# BackPlane.net
KiCad netlist of a schematic drawn in EAGLE
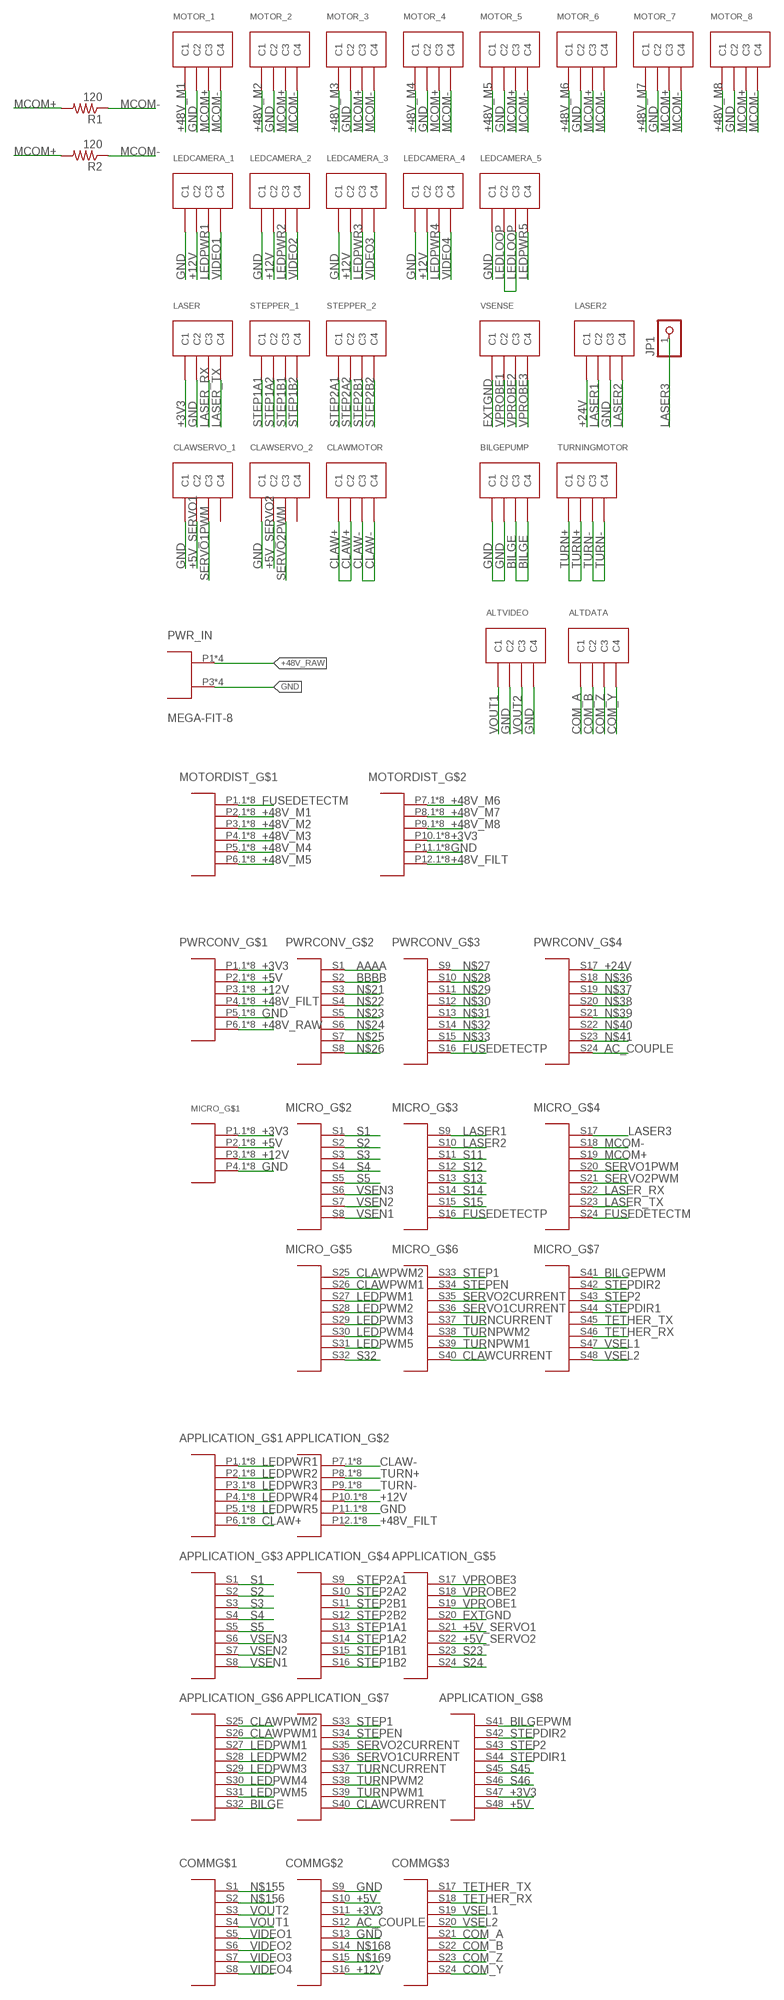
[diagram p0: schematic, sheet 1]

(export (version "E")
  (design (tool "Eeschema 10.0.6"))
  (components
    (comp (ref "ALTDATA")
      (value "MICRO-FIT-4-SMD-PART")
      (footprint "eagle-import:MIRCO-FIT-4-SMD")
      (libsource (lib "eagle-import") (part "MICRO-FIT-4-SMD-PART"))
    )
    (comp (ref "ALTVIDEO")
      (value "MICRO-FIT-4-SMD-PART")
      (footprint "eagle-import:MIRCO-FIT-4-SMD")
      (libsource (lib "eagle-import") (part "MICRO-FIT-4-SMD-PART"))
    )
    (comp (ref "APPLICATION_")
      (value "TEN60-P6-S24-S24-P6-VERT")
      (footprint "eagle-import:TEN60-P6-S24-S24-P6-VERT")
      (libsource (lib "eagle-import") (part "TEN60-P6-S24-S24-P6-VERT"))
    )
    (comp (ref "BILGEPUMP")
      (value "MICRO-FIT-4-SMD-PART")
      (footprint "eagle-import:MIRCO-FIT-4-SMD")
      (libsource (lib "eagle-import") (part "MICRO-FIT-4-SMD-PART"))
    )
    (comp (ref "CLAWMOTOR")
      (value "MICRO-FIT-4-SMD-PART")
      (footprint "eagle-import:MIRCO-FIT-4-SMD")
      (libsource (lib "eagle-import") (part "MICRO-FIT-4-SMD-PART"))
    )
    (comp (ref "CLAWSERVO_1")
      (value "MICRO-FIT-4-SMD-PART")
      (footprint "eagle-import:MIRCO-FIT-4-SMD")
      (libsource (lib "eagle-import") (part "MICRO-FIT-4-SMD-PART"))
    )
    (comp (ref "CLAWSERVO_2")
      (value "MICRO-FIT-4-SMD-PART")
      (footprint "eagle-import:MIRCO-FIT-4-SMD")
      (libsource (lib "eagle-import") (part "MICRO-FIT-4-SMD-PART"))
    )
    (comp (ref "COMM")
      (value "TEN60-S24-RA")
      (footprint "eagle-import:TEN60-S24-RA")
      (libsource (lib "eagle-import") (part "TEN60-S24-RA"))
    )
    (comp (ref "JP1")
      (value "PINHD-1X1")
      (footprint "eagle-import:1X01")
      (libsource (lib "eagle-import") (part "PINHD-1X1"))
    )
    (comp (ref "LASER")
      (value "MICRO-FIT-4-SMD-PART")
      (footprint "eagle-import:MIRCO-FIT-4-SMD")
      (libsource (lib "eagle-import") (part "MICRO-FIT-4-SMD-PART"))
    )
    (comp (ref "LASER2")
      (value "MICRO-FIT-4-SMD-PART")
      (footprint "eagle-import:MIRCO-FIT-4-SMD")
      (libsource (lib "eagle-import") (part "MICRO-FIT-4-SMD-PART"))
    )
    (comp (ref "LEDCAMERA_1")
      (value "MICRO-FIT-4-SMD-PART")
      (footprint "eagle-import:MIRCO-FIT-4-SMD")
      (libsource (lib "eagle-import") (part "MICRO-FIT-4-SMD-PART"))
    )
    (comp (ref "LEDCAMERA_2")
      (value "MICRO-FIT-4-SMD-PART")
      (footprint "eagle-import:MIRCO-FIT-4-SMD")
      (libsource (lib "eagle-import") (part "MICRO-FIT-4-SMD-PART"))
    )
    (comp (ref "LEDCAMERA_3")
      (value "MICRO-FIT-4-SMD-PART")
      (footprint "eagle-import:MIRCO-FIT-4-SMD")
      (libsource (lib "eagle-import") (part "MICRO-FIT-4-SMD-PART"))
    )
    (comp (ref "LEDCAMERA_4")
      (value "MICRO-FIT-4-SMD-PART")
      (footprint "eagle-import:MIRCO-FIT-4-SMD")
      (libsource (lib "eagle-import") (part "MICRO-FIT-4-SMD-PART"))
    )
    (comp (ref "LEDCAMERA_5")
      (value "MICRO-FIT-4-SMD-PART")
      (footprint "eagle-import:MIRCO-FIT-4-SMD")
      (libsource (lib "eagle-import") (part "MICRO-FIT-4-SMD-PART"))
    )
    (comp (ref "MICRO_")
      (value "TEN60-S24-S24-P4-VERT")
      (footprint "eagle-import:TEN60-S24-S24-P4-VERT")
      (libsource (lib "eagle-import") (part "TEN60-S24-S24-P4-VERT"))
    )
    (comp (ref "MOTORDIST_")
      (value "TEN60-P6-P6-VERT")
      (footprint "eagle-import:TEN60-P6-P6-VERT")
      (libsource (lib "eagle-import") (part "TEN60-P6-P6-VERT"))
    )
    (comp (ref "MOTOR_1")
      (value "MICRO-FIT-4-SMD-PART")
      (footprint "eagle-import:MIRCO-FIT-4-SMD")
      (libsource (lib "eagle-import") (part "MICRO-FIT-4-SMD-PART"))
    )
    (comp (ref "MOTOR_2")
      (value "MICRO-FIT-4-SMD-PART")
      (footprint "eagle-import:MIRCO-FIT-4-SMD")
      (libsource (lib "eagle-import") (part "MICRO-FIT-4-SMD-PART"))
    )
    (comp (ref "MOTOR_3")
      (value "MICRO-FIT-4-SMD-PART")
      (footprint "eagle-import:MIRCO-FIT-4-SMD")
      (libsource (lib "eagle-import") (part "MICRO-FIT-4-SMD-PART"))
    )
    (comp (ref "MOTOR_4")
      (value "MICRO-FIT-4-SMD-PART")
      (footprint "eagle-import:MIRCO-FIT-4-SMD")
      (libsource (lib "eagle-import") (part "MICRO-FIT-4-SMD-PART"))
    )
    (comp (ref "MOTOR_5")
      (value "MICRO-FIT-4-SMD-PART")
      (footprint "eagle-import:MIRCO-FIT-4-SMD")
      (libsource (lib "eagle-import") (part "MICRO-FIT-4-SMD-PART"))
    )
    (comp (ref "MOTOR_6")
      (value "MICRO-FIT-4-SMD-PART")
      (footprint "eagle-import:MIRCO-FIT-4-SMD")
      (libsource (lib "eagle-import") (part "MICRO-FIT-4-SMD-PART"))
    )
    (comp (ref "MOTOR_7")
      (value "MICRO-FIT-4-SMD-PART")
      (footprint "eagle-import:MIRCO-FIT-4-SMD")
      (libsource (lib "eagle-import") (part "MICRO-FIT-4-SMD-PART"))
    )
    (comp (ref "MOTOR_8")
      (value "MICRO-FIT-4-SMD-PART")
      (footprint "eagle-import:MIRCO-FIT-4-SMD")
      (libsource (lib "eagle-import") (part "MICRO-FIT-4-SMD-PART"))
    )
    (comp (ref "PWRCONV_")
      (value "TEN60-S24-P6-VERT")
      (footprint "eagle-import:TEN60-S24-P6-VERT")
      (libsource (lib "eagle-import") (part "TEN60-S24-P6-VERT"))
    )
    (comp (ref "PWR_IN")
      (value "MEGA-FIT-8")
      (footprint "eagle-import:MEGA-FIT-8")
      (libsource (lib "eagle-import") (part "MEGA-FIT-8"))
    )
    (comp (ref "R1")
      (value "120")
      (footprint "eagle-import:R0603")
      (libsource (lib "eagle-import") (part "R-US_R0603"))
    )
    (comp (ref "R2")
      (value "120")
      (footprint "eagle-import:R0603")
      (libsource (lib "eagle-import") (part "R-US_R0603"))
    )
    (comp (ref "STEPPER_1")
      (value "MICRO-FIT-4-SMD-PART")
      (footprint "eagle-import:MIRCO-FIT-4-SMD")
      (libsource (lib "eagle-import") (part "MICRO-FIT-4-SMD-PART"))
    )
    (comp (ref "STEPPER_2")
      (value "MICRO-FIT-4-SMD-PART")
      (footprint "eagle-import:MIRCO-FIT-4-SMD")
      (libsource (lib "eagle-import") (part "MICRO-FIT-4-SMD-PART"))
    )
    (comp (ref "TURNINGMOTOR")
      (value "MICRO-FIT-4-SMD-PART")
      (footprint "eagle-import:MIRCO-FIT-4-SMD")
      (libsource (lib "eagle-import") (part "MICRO-FIT-4-SMD-PART"))
    )
    (comp (ref "VSENSE")
      (value "MICRO-FIT-4-SMD-PART")
      (footprint "eagle-import:MIRCO-FIT-4-SMD")
      (libsource (lib "eagle-import") (part "MICRO-FIT-4-SMD-PART"))
    )
  )
  (nets
    (net (code "1") (name "+48V_RAW") (class "Default")
      (node (ref "PWRCONV_") (pin "P6.1") (pinfunction "P$6_P6.1") (pintype "bidirectional"))
      (node (ref "PWRCONV_") (pin "P6.2") (pinfunction "P$6_P6.2") (pintype "bidirectional"))
      (node (ref "PWRCONV_") (pin "P6.3") (pinfunction "P$6_P6.3") (pintype "bidirectional"))
      (node (ref "PWRCONV_") (pin "P6.4") (pinfunction "P$6_P6.4") (pintype "bidirectional"))
      (node (ref "PWRCONV_") (pin "P6.5") (pinfunction "P$6_P6.5") (pintype "bidirectional"))
      (node (ref "PWRCONV_") (pin "P6.6") (pinfunction "P$6_P6.6") (pintype "bidirectional"))
      (node (ref "PWRCONV_") (pin "P6.7") (pinfunction "P$6_P6.7") (pintype "bidirectional"))
      (node (ref "PWRCONV_") (pin "P6.8") (pinfunction "P$6_P6.8") (pintype "bidirectional"))
      (node (ref "PWR_IN") (pin "P1") (pinfunction "P$1_P1") (pintype "bidirectional"))
      (node (ref "PWR_IN") (pin "P2") (pinfunction "P$1_P2") (pintype "bidirectional"))
      (node (ref "PWR_IN") (pin "P5") (pinfunction "P$1_P5") (pintype "bidirectional"))
      (node (ref "PWR_IN") (pin "P6") (pinfunction "P$1_P6") (pintype "bidirectional"))
    )
    (net (code "2") (name "/+3V3") (class "Default")
      (node (ref "APPLICATION_") (pin "S47") (pinfunction "P$7_S47") (pintype "bidirectional"))
      (node (ref "COMM") (pin "S11") (pinfunction "P$3_S11") (pintype "bidirectional"))
      (node (ref "LASER") (pin "C1") (pinfunction "C1_C1") (pintype "bidirectional"))
      (node (ref "MICRO_") (pin "P1.1") (pinfunction "P$1_P1.1") (pintype "bidirectional"))
      (node (ref "MICRO_") (pin "P1.2") (pinfunction "P$1_P1.2") (pintype "bidirectional"))
      (node (ref "MICRO_") (pin "P1.3") (pinfunction "P$1_P1.3") (pintype "bidirectional"))
      (node (ref "MICRO_") (pin "P1.4") (pinfunction "P$1_P1.4") (pintype "bidirectional"))
      (node (ref "MICRO_") (pin "P1.5") (pinfunction "P$1_P1.5") (pintype "bidirectional"))
      (node (ref "MICRO_") (pin "P1.6") (pinfunction "P$1_P1.6") (pintype "bidirectional"))
      (node (ref "MICRO_") (pin "P1.7") (pinfunction "P$1_P1.7") (pintype "bidirectional"))
      (node (ref "MICRO_") (pin "P1.8") (pinfunction "P$1_P1.8") (pintype "bidirectional"))
      (node (ref "MOTORDIST_") (pin "P10.1") (pinfunction "P$4_P10.1") (pintype "bidirectional"))
      (node (ref "MOTORDIST_") (pin "P10.2") (pinfunction "P$4_P10.2") (pintype "bidirectional"))
      (node (ref "MOTORDIST_") (pin "P10.3") (pinfunction "P$4_P10.3") (pintype "bidirectional"))
      (node (ref "MOTORDIST_") (pin "P10.4") (pinfunction "P$4_P10.4") (pintype "bidirectional"))
      (node (ref "MOTORDIST_") (pin "P10.5") (pinfunction "P$4_P10.5") (pintype "bidirectional"))
      (node (ref "MOTORDIST_") (pin "P10.6") (pinfunction "P$4_P10.6") (pintype "bidirectional"))
      (node (ref "MOTORDIST_") (pin "P10.7") (pinfunction "P$4_P10.7") (pintype "bidirectional"))
      (node (ref "MOTORDIST_") (pin "P10.8") (pinfunction "P$4_P10.8") (pintype "bidirectional"))
      (node (ref "PWRCONV_") (pin "P1.1") (pinfunction "P$1_P1.1") (pintype "bidirectional"))
      (node (ref "PWRCONV_") (pin "P1.2") (pinfunction "P$1_P1.2") (pintype "bidirectional"))
      (node (ref "PWRCONV_") (pin "P1.3") (pinfunction "P$1_P1.3") (pintype "bidirectional"))
      (node (ref "PWRCONV_") (pin "P1.4") (pinfunction "P$1_P1.4") (pintype "bidirectional"))
      (node (ref "PWRCONV_") (pin "P1.5") (pinfunction "P$1_P1.5") (pintype "bidirectional"))
      (node (ref "PWRCONV_") (pin "P1.6") (pinfunction "P$1_P1.6") (pintype "bidirectional"))
      (node (ref "PWRCONV_") (pin "P1.7") (pinfunction "P$1_P1.7") (pintype "bidirectional"))
      (node (ref "PWRCONV_") (pin "P1.8") (pinfunction "P$1_P1.8") (pintype "bidirectional"))
    )
    (net (code "3") (name "/+5V") (class "Default")
      (node (ref "APPLICATION_") (pin "S48") (pinfunction "P$8_S48") (pintype "bidirectional"))
      (node (ref "COMM") (pin "S10") (pinfunction "P$2_S10") (pintype "bidirectional"))
      (node (ref "MICRO_") (pin "P2.1") (pinfunction "P$2_P2.1") (pintype "bidirectional"))
      (node (ref "MICRO_") (pin "P2.2") (pinfunction "P$2_P2.2") (pintype "bidirectional"))
      (node (ref "MICRO_") (pin "P2.3") (pinfunction "P$2_P2.3") (pintype "bidirectional"))
      (node (ref "MICRO_") (pin "P2.4") (pinfunction "P$2_P2.4") (pintype "bidirectional"))
      (node (ref "MICRO_") (pin "P2.5") (pinfunction "P$2_P2.5") (pintype "bidirectional"))
      (node (ref "MICRO_") (pin "P2.6") (pinfunction "P$2_P2.6") (pintype "bidirectional"))
      (node (ref "MICRO_") (pin "P2.7") (pinfunction "P$2_P2.7") (pintype "bidirectional"))
      (node (ref "MICRO_") (pin "P2.8") (pinfunction "P$2_P2.8") (pintype "bidirectional"))
      (node (ref "PWRCONV_") (pin "P2.1") (pinfunction "P$2_P2.1") (pintype "bidirectional"))
      (node (ref "PWRCONV_") (pin "P2.2") (pinfunction "P$2_P2.2") (pintype "bidirectional"))
      (node (ref "PWRCONV_") (pin "P2.3") (pinfunction "P$2_P2.3") (pintype "bidirectional"))
      (node (ref "PWRCONV_") (pin "P2.4") (pinfunction "P$2_P2.4") (pintype "bidirectional"))
      (node (ref "PWRCONV_") (pin "P2.5") (pinfunction "P$2_P2.5") (pintype "bidirectional"))
      (node (ref "PWRCONV_") (pin "P2.6") (pinfunction "P$2_P2.6") (pintype "bidirectional"))
      (node (ref "PWRCONV_") (pin "P2.7") (pinfunction "P$2_P2.7") (pintype "bidirectional"))
      (node (ref "PWRCONV_") (pin "P2.8") (pinfunction "P$2_P2.8") (pintype "bidirectional"))
    )
    (net (code "4") (name "/+5V_SERVO1") (class "Default")
      (node (ref "APPLICATION_") (pin "S21") (pinfunction "P$5_S21") (pintype "bidirectional"))
      (node (ref "CLAWSERVO_1") (pin "C2") (pinfunction "C2_C2") (pintype "bidirectional"))
    )
    (net (code "5") (name "/+5V_SERVO2") (class "Default")
      (node (ref "APPLICATION_") (pin "S22") (pinfunction "P$6_S22") (pintype "bidirectional"))
      (node (ref "CLAWSERVO_2") (pin "C2") (pinfunction "C2_C2") (pintype "bidirectional"))
    )
    (net (code "6") (name "/+12V") (class "Default")
      (node (ref "APPLICATION_") (pin "P10.1") (pinfunction "P$4_P10.1") (pintype "bidirectional"))
      (node (ref "APPLICATION_") (pin "P10.2") (pinfunction "P$4_P10.2") (pintype "bidirectional"))
      (node (ref "APPLICATION_") (pin "P10.3") (pinfunction "P$4_P10.3") (pintype "bidirectional"))
      (node (ref "APPLICATION_") (pin "P10.4") (pinfunction "P$4_P10.4") (pintype "bidirectional"))
      (node (ref "APPLICATION_") (pin "P10.5") (pinfunction "P$4_P10.5") (pintype "bidirectional"))
      (node (ref "APPLICATION_") (pin "P10.6") (pinfunction "P$4_P10.6") (pintype "bidirectional"))
      (node (ref "APPLICATION_") (pin "P10.7") (pinfunction "P$4_P10.7") (pintype "bidirectional"))
      (node (ref "APPLICATION_") (pin "P10.8") (pinfunction "P$4_P10.8") (pintype "bidirectional"))
      (node (ref "COMM") (pin "S16") (pinfunction "P$8_S16") (pintype "bidirectional"))
      (node (ref "LEDCAMERA_1") (pin "C2") (pinfunction "C2_C2") (pintype "bidirectional"))
      (node (ref "LEDCAMERA_2") (pin "C2") (pinfunction "C2_C2") (pintype "bidirectional"))
      (node (ref "LEDCAMERA_3") (pin "C2") (pinfunction "C2_C2") (pintype "bidirectional"))
      (node (ref "LEDCAMERA_4") (pin "C2") (pinfunction "C2_C2") (pintype "bidirectional"))
      (node (ref "MICRO_") (pin "P3.1") (pinfunction "P$3_P3.1") (pintype "bidirectional"))
      (node (ref "MICRO_") (pin "P3.2") (pinfunction "P$3_P3.2") (pintype "bidirectional"))
      (node (ref "MICRO_") (pin "P3.3") (pinfunction "P$3_P3.3") (pintype "bidirectional"))
      (node (ref "MICRO_") (pin "P3.4") (pinfunction "P$3_P3.4") (pintype "bidirectional"))
      (node (ref "MICRO_") (pin "P3.5") (pinfunction "P$3_P3.5") (pintype "bidirectional"))
      (node (ref "MICRO_") (pin "P3.6") (pinfunction "P$3_P3.6") (pintype "bidirectional"))
      (node (ref "MICRO_") (pin "P3.7") (pinfunction "P$3_P3.7") (pintype "bidirectional"))
      (node (ref "MICRO_") (pin "P3.8") (pinfunction "P$3_P3.8") (pintype "bidirectional"))
      (node (ref "PWRCONV_") (pin "P3.1") (pinfunction "P$3_P3.1") (pintype "bidirectional"))
      (node (ref "PWRCONV_") (pin "P3.2") (pinfunction "P$3_P3.2") (pintype "bidirectional"))
      (node (ref "PWRCONV_") (pin "P3.3") (pinfunction "P$3_P3.3") (pintype "bidirectional"))
      (node (ref "PWRCONV_") (pin "P3.4") (pinfunction "P$3_P3.4") (pintype "bidirectional"))
      (node (ref "PWRCONV_") (pin "P3.5") (pinfunction "P$3_P3.5") (pintype "bidirectional"))
      (node (ref "PWRCONV_") (pin "P3.6") (pinfunction "P$3_P3.6") (pintype "bidirectional"))
      (node (ref "PWRCONV_") (pin "P3.7") (pinfunction "P$3_P3.7") (pintype "bidirectional"))
      (node (ref "PWRCONV_") (pin "P3.8") (pinfunction "P$3_P3.8") (pintype "bidirectional"))
    )
    (net (code "7") (name "/+24V") (class "Default")
      (node (ref "LASER2") (pin "C1") (pinfunction "C1_C1") (pintype "bidirectional"))
      (node (ref "PWRCONV_") (pin "S17") (pinfunction "P$1_S17") (pintype "bidirectional"))
    )
    (net (code "8") (name "/+48V_FILT") (class "Default")
      (node (ref "APPLICATION_") (pin "P12.1") (pinfunction "P$6_P12.1") (pintype "bidirectional"))
      (node (ref "APPLICATION_") (pin "P12.2") (pinfunction "P$6_P12.2") (pintype "bidirectional"))
      (node (ref "APPLICATION_") (pin "P12.3") (pinfunction "P$6_P12.3") (pintype "bidirectional"))
      (node (ref "APPLICATION_") (pin "P12.4") (pinfunction "P$6_P12.4") (pintype "bidirectional"))
      (node (ref "APPLICATION_") (pin "P12.5") (pinfunction "P$6_P12.5") (pintype "bidirectional"))
      (node (ref "APPLICATION_") (pin "P12.6") (pinfunction "P$6_P12.6") (pintype "bidirectional"))
      (node (ref "APPLICATION_") (pin "P12.7") (pinfunction "P$6_P12.7") (pintype "bidirectional"))
      (node (ref "APPLICATION_") (pin "P12.8") (pinfunction "P$6_P12.8") (pintype "bidirectional"))
      (node (ref "MOTORDIST_") (pin "P12.1") (pinfunction "P$6_P12.1") (pintype "bidirectional"))
      (node (ref "MOTORDIST_") (pin "P12.2") (pinfunction "P$6_P12.2") (pintype "bidirectional"))
      (node (ref "MOTORDIST_") (pin "P12.3") (pinfunction "P$6_P12.3") (pintype "bidirectional"))
      (node (ref "MOTORDIST_") (pin "P12.4") (pinfunction "P$6_P12.4") (pintype "bidirectional"))
      (node (ref "MOTORDIST_") (pin "P12.5") (pinfunction "P$6_P12.5") (pintype "bidirectional"))
      (node (ref "MOTORDIST_") (pin "P12.6") (pinfunction "P$6_P12.6") (pintype "bidirectional"))
      (node (ref "MOTORDIST_") (pin "P12.7") (pinfunction "P$6_P12.7") (pintype "bidirectional"))
      (node (ref "MOTORDIST_") (pin "P12.8") (pinfunction "P$6_P12.8") (pintype "bidirectional"))
      (node (ref "PWRCONV_") (pin "P4.1") (pinfunction "P$4_P4.1") (pintype "bidirectional"))
      (node (ref "PWRCONV_") (pin "P4.2") (pinfunction "P$4_P4.2") (pintype "bidirectional"))
      (node (ref "PWRCONV_") (pin "P4.3") (pinfunction "P$4_P4.3") (pintype "bidirectional"))
      (node (ref "PWRCONV_") (pin "P4.4") (pinfunction "P$4_P4.4") (pintype "bidirectional"))
      (node (ref "PWRCONV_") (pin "P4.5") (pinfunction "P$4_P4.5") (pintype "bidirectional"))
      (node (ref "PWRCONV_") (pin "P4.6") (pinfunction "P$4_P4.6") (pintype "bidirectional"))
      (node (ref "PWRCONV_") (pin "P4.7") (pinfunction "P$4_P4.7") (pintype "bidirectional"))
      (node (ref "PWRCONV_") (pin "P4.8") (pinfunction "P$4_P4.8") (pintype "bidirectional"))
    )
    (net (code "9") (name "/+48V_M1") (class "Default")
      (node (ref "MOTORDIST_") (pin "P2.1") (pinfunction "P$2_P2.1") (pintype "bidirectional"))
      (node (ref "MOTORDIST_") (pin "P2.2") (pinfunction "P$2_P2.2") (pintype "bidirectional"))
      (node (ref "MOTORDIST_") (pin "P2.3") (pinfunction "P$2_P2.3") (pintype "bidirectional"))
      (node (ref "MOTORDIST_") (pin "P2.4") (pinfunction "P$2_P2.4") (pintype "bidirectional"))
      (node (ref "MOTORDIST_") (pin "P2.5") (pinfunction "P$2_P2.5") (pintype "bidirectional"))
      (node (ref "MOTORDIST_") (pin "P2.6") (pinfunction "P$2_P2.6") (pintype "bidirectional"))
      (node (ref "MOTORDIST_") (pin "P2.7") (pinfunction "P$2_P2.7") (pintype "bidirectional"))
      (node (ref "MOTORDIST_") (pin "P2.8") (pinfunction "P$2_P2.8") (pintype "bidirectional"))
      (node (ref "MOTOR_1") (pin "C1") (pinfunction "C1_C1") (pintype "bidirectional"))
    )
    (net (code "10") (name "/+48V_M2") (class "Default")
      (node (ref "MOTORDIST_") (pin "P3.1") (pinfunction "P$3_P3.1") (pintype "bidirectional"))
      (node (ref "MOTORDIST_") (pin "P3.2") (pinfunction "P$3_P3.2") (pintype "bidirectional"))
      (node (ref "MOTORDIST_") (pin "P3.3") (pinfunction "P$3_P3.3") (pintype "bidirectional"))
      (node (ref "MOTORDIST_") (pin "P3.4") (pinfunction "P$3_P3.4") (pintype "bidirectional"))
      (node (ref "MOTORDIST_") (pin "P3.5") (pinfunction "P$3_P3.5") (pintype "bidirectional"))
      (node (ref "MOTORDIST_") (pin "P3.6") (pinfunction "P$3_P3.6") (pintype "bidirectional"))
      (node (ref "MOTORDIST_") (pin "P3.7") (pinfunction "P$3_P3.7") (pintype "bidirectional"))
      (node (ref "MOTORDIST_") (pin "P3.8") (pinfunction "P$3_P3.8") (pintype "bidirectional"))
      (node (ref "MOTOR_2") (pin "C1") (pinfunction "C1_C1") (pintype "bidirectional"))
    )
    (net (code "11") (name "/+48V_M3") (class "Default")
      (node (ref "MOTORDIST_") (pin "P4.1") (pinfunction "P$4_P4.1") (pintype "bidirectional"))
      (node (ref "MOTORDIST_") (pin "P4.2") (pinfunction "P$4_P4.2") (pintype "bidirectional"))
      (node (ref "MOTORDIST_") (pin "P4.3") (pinfunction "P$4_P4.3") (pintype "bidirectional"))
      (node (ref "MOTORDIST_") (pin "P4.4") (pinfunction "P$4_P4.4") (pintype "bidirectional"))
      (node (ref "MOTORDIST_") (pin "P4.5") (pinfunction "P$4_P4.5") (pintype "bidirectional"))
      (node (ref "MOTORDIST_") (pin "P4.6") (pinfunction "P$4_P4.6") (pintype "bidirectional"))
      (node (ref "MOTORDIST_") (pin "P4.7") (pinfunction "P$4_P4.7") (pintype "bidirectional"))
      (node (ref "MOTORDIST_") (pin "P4.8") (pinfunction "P$4_P4.8") (pintype "bidirectional"))
      (node (ref "MOTOR_3") (pin "C1") (pinfunction "C1_C1") (pintype "bidirectional"))
    )
    (net (code "12") (name "/+48V_M4") (class "Default")
      (node (ref "MOTORDIST_") (pin "P5.1") (pinfunction "P$5_P5.1") (pintype "bidirectional"))
      (node (ref "MOTORDIST_") (pin "P5.2") (pinfunction "P$5_P5.2") (pintype "bidirectional"))
      (node (ref "MOTORDIST_") (pin "P5.3") (pinfunction "P$5_P5.3") (pintype "bidirectional"))
      (node (ref "MOTORDIST_") (pin "P5.4") (pinfunction "P$5_P5.4") (pintype "bidirectional"))
      (node (ref "MOTORDIST_") (pin "P5.5") (pinfunction "P$5_P5.5") (pintype "bidirectional"))
      (node (ref "MOTORDIST_") (pin "P5.6") (pinfunction "P$5_P5.6") (pintype "bidirectional"))
      (node (ref "MOTORDIST_") (pin "P5.7") (pinfunction "P$5_P5.7") (pintype "bidirectional"))
      (node (ref "MOTORDIST_") (pin "P5.8") (pinfunction "P$5_P5.8") (pintype "bidirectional"))
      (node (ref "MOTOR_4") (pin "C1") (pinfunction "C1_C1") (pintype "bidirectional"))
    )
    (net (code "13") (name "/+48V_M5") (class "Default")
      (node (ref "MOTORDIST_") (pin "P6.1") (pinfunction "P$6_P6.1") (pintype "bidirectional"))
      (node (ref "MOTORDIST_") (pin "P6.2") (pinfunction "P$6_P6.2") (pintype "bidirectional"))
      (node (ref "MOTORDIST_") (pin "P6.3") (pinfunction "P$6_P6.3") (pintype "bidirectional"))
      (node (ref "MOTORDIST_") (pin "P6.4") (pinfunction "P$6_P6.4") (pintype "bidirectional"))
      (node (ref "MOTORDIST_") (pin "P6.5") (pinfunction "P$6_P6.5") (pintype "bidirectional"))
      (node (ref "MOTORDIST_") (pin "P6.6") (pinfunction "P$6_P6.6") (pintype "bidirectional"))
      (node (ref "MOTORDIST_") (pin "P6.7") (pinfunction "P$6_P6.7") (pintype "bidirectional"))
      (node (ref "MOTORDIST_") (pin "P6.8") (pinfunction "P$6_P6.8") (pintype "bidirectional"))
      (node (ref "MOTOR_5") (pin "C1") (pinfunction "C1_C1") (pintype "bidirectional"))
    )
    (net (code "14") (name "/+48V_M6") (class "Default")
      (node (ref "MOTORDIST_") (pin "P7.1") (pinfunction "P$1_P7.1") (pintype "bidirectional"))
      (node (ref "MOTORDIST_") (pin "P7.2") (pinfunction "P$1_P7.2") (pintype "bidirectional"))
      (node (ref "MOTORDIST_") (pin "P7.3") (pinfunction "P$1_P7.3") (pintype "bidirectional"))
      (node (ref "MOTORDIST_") (pin "P7.4") (pinfunction "P$1_P7.4") (pintype "bidirectional"))
      (node (ref "MOTORDIST_") (pin "P7.5") (pinfunction "P$1_P7.5") (pintype "bidirectional"))
      (node (ref "MOTORDIST_") (pin "P7.6") (pinfunction "P$1_P7.6") (pintype "bidirectional"))
      (node (ref "MOTORDIST_") (pin "P7.7") (pinfunction "P$1_P7.7") (pintype "bidirectional"))
      (node (ref "MOTORDIST_") (pin "P7.8") (pinfunction "P$1_P7.8") (pintype "bidirectional"))
      (node (ref "MOTOR_6") (pin "C1") (pinfunction "C1_C1") (pintype "bidirectional"))
    )
    (net (code "15") (name "/+48V_M7") (class "Default")
      (node (ref "MOTORDIST_") (pin "P8.1") (pinfunction "P$2_P8.1") (pintype "bidirectional"))
      (node (ref "MOTORDIST_") (pin "P8.2") (pinfunction "P$2_P8.2") (pintype "bidirectional"))
      (node (ref "MOTORDIST_") (pin "P8.3") (pinfunction "P$2_P8.3") (pintype "bidirectional"))
      (node (ref "MOTORDIST_") (pin "P8.4") (pinfunction "P$2_P8.4") (pintype "bidirectional"))
      (node (ref "MOTORDIST_") (pin "P8.5") (pinfunction "P$2_P8.5") (pintype "bidirectional"))
      (node (ref "MOTORDIST_") (pin "P8.6") (pinfunction "P$2_P8.6") (pintype "bidirectional"))
      (node (ref "MOTORDIST_") (pin "P8.7") (pinfunction "P$2_P8.7") (pintype "bidirectional"))
      (node (ref "MOTORDIST_") (pin "P8.8") (pinfunction "P$2_P8.8") (pintype "bidirectional"))
      (node (ref "MOTOR_7") (pin "C1") (pinfunction "C1_C1") (pintype "bidirectional"))
    )
    (net (code "16") (name "/+48V_M8") (class "Default")
      (node (ref "MOTORDIST_") (pin "P9.1") (pinfunction "P$3_P9.1") (pintype "bidirectional"))
      (node (ref "MOTORDIST_") (pin "P9.2") (pinfunction "P$3_P9.2") (pintype "bidirectional"))
      (node (ref "MOTORDIST_") (pin "P9.3") (pinfunction "P$3_P9.3") (pintype "bidirectional"))
      (node (ref "MOTORDIST_") (pin "P9.4") (pinfunction "P$3_P9.4") (pintype "bidirectional"))
      (node (ref "MOTORDIST_") (pin "P9.5") (pinfunction "P$3_P9.5") (pintype "bidirectional"))
      (node (ref "MOTORDIST_") (pin "P9.6") (pinfunction "P$3_P9.6") (pintype "bidirectional"))
      (node (ref "MOTORDIST_") (pin "P9.7") (pinfunction "P$3_P9.7") (pintype "bidirectional"))
      (node (ref "MOTORDIST_") (pin "P9.8") (pinfunction "P$3_P9.8") (pintype "bidirectional"))
      (node (ref "MOTOR_8") (pin "C1") (pinfunction "C1_C1") (pintype "bidirectional"))
    )
    (net (code "17") (name "/AAAA") (class "Default")
      (node (ref "PWRCONV_") (pin "S1") (pinfunction "P$1_S1") (pintype "bidirectional"))
    )
    (net (code "18") (name "/AC_COUPLE") (class "Default")
      (node (ref "COMM") (pin "S12") (pinfunction "P$4_S12") (pintype "bidirectional"))
      (node (ref "PWRCONV_") (pin "S24") (pinfunction "P$8_S24") (pintype "bidirectional"))
    )
    (net (code "19") (name "/BBBB") (class "Default")
      (node (ref "PWRCONV_") (pin "S2") (pinfunction "P$2_S2") (pintype "bidirectional"))
    )
    (net (code "20") (name "/BILGE") (class "Default")
      (node (ref "APPLICATION_") (pin "S32") (pinfunction "P$8_S32") (pintype "bidirectional"))
      (node (ref "BILGEPUMP") (pin "C3") (pinfunction "C3_C3") (pintype "bidirectional"))
      (node (ref "BILGEPUMP") (pin "C4") (pinfunction "C4_C4") (pintype "bidirectional"))
    )
    (net (code "21") (name "/BILGEPWM") (class "Default")
      (node (ref "APPLICATION_") (pin "S41") (pinfunction "P$1_S41") (pintype "bidirectional"))
      (node (ref "MICRO_") (pin "S41") (pinfunction "P$1_S41") (pintype "bidirectional"))
    )
    (net (code "22") (name "/CLAW+") (class "Default")
      (node (ref "APPLICATION_") (pin "P6.1") (pinfunction "P$6_P6.1") (pintype "bidirectional"))
      (node (ref "APPLICATION_") (pin "P6.2") (pinfunction "P$6_P6.2") (pintype "bidirectional"))
      (node (ref "APPLICATION_") (pin "P6.3") (pinfunction "P$6_P6.3") (pintype "bidirectional"))
      (node (ref "APPLICATION_") (pin "P6.4") (pinfunction "P$6_P6.4") (pintype "bidirectional"))
      (node (ref "APPLICATION_") (pin "P6.5") (pinfunction "P$6_P6.5") (pintype "bidirectional"))
      (node (ref "APPLICATION_") (pin "P6.6") (pinfunction "P$6_P6.6") (pintype "bidirectional"))
      (node (ref "APPLICATION_") (pin "P6.7") (pinfunction "P$6_P6.7") (pintype "bidirectional"))
      (node (ref "APPLICATION_") (pin "P6.8") (pinfunction "P$6_P6.8") (pintype "bidirectional"))
      (node (ref "CLAWMOTOR") (pin "C1") (pinfunction "C1_C1") (pintype "bidirectional"))
      (node (ref "CLAWMOTOR") (pin "C2") (pinfunction "C2_C2") (pintype "bidirectional"))
    )
    (net (code "23") (name "/CLAW-") (class "Default")
      (node (ref "APPLICATION_") (pin "P7.1") (pinfunction "P$1_P7.1") (pintype "bidirectional"))
      (node (ref "APPLICATION_") (pin "P7.2") (pinfunction "P$1_P7.2") (pintype "bidirectional"))
      (node (ref "APPLICATION_") (pin "P7.3") (pinfunction "P$1_P7.3") (pintype "bidirectional"))
      (node (ref "APPLICATION_") (pin "P7.4") (pinfunction "P$1_P7.4") (pintype "bidirectional"))
      (node (ref "APPLICATION_") (pin "P7.5") (pinfunction "P$1_P7.5") (pintype "bidirectional"))
      (node (ref "APPLICATION_") (pin "P7.6") (pinfunction "P$1_P7.6") (pintype "bidirectional"))
      (node (ref "APPLICATION_") (pin "P7.7") (pinfunction "P$1_P7.7") (pintype "bidirectional"))
      (node (ref "APPLICATION_") (pin "P7.8") (pinfunction "P$1_P7.8") (pintype "bidirectional"))
      (node (ref "CLAWMOTOR") (pin "C3") (pinfunction "C3_C3") (pintype "bidirectional"))
      (node (ref "CLAWMOTOR") (pin "C4") (pinfunction "C4_C4") (pintype "bidirectional"))
    )
    (net (code "24") (name "/CLAWCURRENT") (class "Default")
      (node (ref "APPLICATION_") (pin "S40") (pinfunction "P$8_S40") (pintype "bidirectional"))
      (node (ref "MICRO_") (pin "S40") (pinfunction "P$8_S40") (pintype "bidirectional"))
    )
    (net (code "25") (name "/CLAWPWM1") (class "Default")
      (node (ref "APPLICATION_") (pin "S26") (pinfunction "P$2_S26") (pintype "bidirectional"))
      (node (ref "MICRO_") (pin "S26") (pinfunction "P$2_S26") (pintype "bidirectional"))
    )
    (net (code "26") (name "/CLAWPWM2") (class "Default")
      (node (ref "APPLICATION_") (pin "S25") (pinfunction "P$1_S25") (pintype "bidirectional"))
      (node (ref "MICRO_") (pin "S25") (pinfunction "P$1_S25") (pintype "bidirectional"))
    )
    (net (code "27") (name "/COM_A") (class "Default")
      (node (ref "ALTDATA") (pin "C1") (pinfunction "C1_C1") (pintype "bidirectional"))
      (node (ref "COMM") (pin "S21") (pinfunction "P$5_S21") (pintype "bidirectional"))
    )
    (net (code "28") (name "/COM_B") (class "Default")
      (node (ref "ALTDATA") (pin "C2") (pinfunction "C2_C2") (pintype "bidirectional"))
      (node (ref "COMM") (pin "S22") (pinfunction "P$6_S22") (pintype "bidirectional"))
    )
    (net (code "29") (name "/COM_Y") (class "Default")
      (node (ref "ALTDATA") (pin "C4") (pinfunction "C4_C4") (pintype "bidirectional"))
      (node (ref "COMM") (pin "S24") (pinfunction "P$8_S24") (pintype "bidirectional"))
    )
    (net (code "30") (name "/COM_Z") (class "Default")
      (node (ref "ALTDATA") (pin "C3") (pinfunction "C3_C3") (pintype "bidirectional"))
      (node (ref "COMM") (pin "S23") (pinfunction "P$7_S23") (pintype "bidirectional"))
    )
    (net (code "31") (name "/EXTGND") (class "Default")
      (node (ref "APPLICATION_") (pin "S20") (pinfunction "P$4_S20") (pintype "bidirectional"))
      (node (ref "VSENSE") (pin "C1") (pinfunction "C1_C1") (pintype "bidirectional"))
    )
    (net (code "32") (name "/FUSEDETECTM") (class "Default")
      (node (ref "MICRO_") (pin "S24") (pinfunction "P$8_S24") (pintype "bidirectional"))
      (node (ref "MOTORDIST_") (pin "P1.1") (pinfunction "P$1_P1.1") (pintype "bidirectional"))
      (node (ref "MOTORDIST_") (pin "P1.2") (pinfunction "P$1_P1.2") (pintype "bidirectional"))
      (node (ref "MOTORDIST_") (pin "P1.3") (pinfunction "P$1_P1.3") (pintype "bidirectional"))
      (node (ref "MOTORDIST_") (pin "P1.4") (pinfunction "P$1_P1.4") (pintype "bidirectional"))
      (node (ref "MOTORDIST_") (pin "P1.5") (pinfunction "P$1_P1.5") (pintype "bidirectional"))
      (node (ref "MOTORDIST_") (pin "P1.6") (pinfunction "P$1_P1.6") (pintype "bidirectional"))
      (node (ref "MOTORDIST_") (pin "P1.7") (pinfunction "P$1_P1.7") (pintype "bidirectional"))
      (node (ref "MOTORDIST_") (pin "P1.8") (pinfunction "P$1_P1.8") (pintype "bidirectional"))
    )
    (net (code "33") (name "/FUSEDETECTP") (class "Default")
      (node (ref "MICRO_") (pin "S16") (pinfunction "P$8_S16") (pintype "bidirectional"))
      (node (ref "PWRCONV_") (pin "S16") (pinfunction "P$8_S16") (pintype "bidirectional"))
    )
    (net (code "34") (name "/LASER1") (class "Default")
      (node (ref "LASER2") (pin "C2") (pinfunction "C2_C2") (pintype "bidirectional"))
      (node (ref "MICRO_") (pin "S9") (pinfunction "P$1_S9") (pintype "bidirectional"))
    )
    (net (code "35") (name "/LASER2") (class "Default")
      (node (ref "LASER2") (pin "C4") (pinfunction "C4_C4") (pintype "bidirectional"))
      (node (ref "MICRO_") (pin "S10") (pinfunction "P$2_S10") (pintype "bidirectional"))
    )
    (net (code "36") (name "/LASER3") (class "Default")
      (node (ref "JP1") (pin "1") (pinfunction "1_1") (pintype "passive"))
      (node (ref "MICRO_") (pin "S17") (pinfunction "P$1_S17") (pintype "bidirectional"))
    )
    (net (code "37") (name "/LASER_RX") (class "Default")
      (node (ref "LASER") (pin "C3") (pinfunction "C3_C3") (pintype "bidirectional"))
      (node (ref "MICRO_") (pin "S22") (pinfunction "P$6_S22") (pintype "bidirectional"))
    )
    (net (code "38") (name "/LASER_TX") (class "Default")
      (node (ref "LASER") (pin "C4") (pinfunction "C4_C4") (pintype "bidirectional"))
      (node (ref "MICRO_") (pin "S23") (pinfunction "P$7_S23") (pintype "bidirectional"))
    )
    (net (code "39") (name "/LEDLOOP") (class "Default")
      (node (ref "LEDCAMERA_5") (pin "C2") (pinfunction "C2_C2") (pintype "bidirectional"))
      (node (ref "LEDCAMERA_5") (pin "C3") (pinfunction "C3_C3") (pintype "bidirectional"))
    )
    (net (code "40") (name "/LEDPWM1") (class "Default")
      (node (ref "APPLICATION_") (pin "S27") (pinfunction "P$3_S27") (pintype "bidirectional"))
      (node (ref "MICRO_") (pin "S27") (pinfunction "P$3_S27") (pintype "bidirectional"))
    )
    (net (code "41") (name "/LEDPWM2") (class "Default")
      (node (ref "APPLICATION_") (pin "S28") (pinfunction "P$4_S28") (pintype "bidirectional"))
      (node (ref "MICRO_") (pin "S28") (pinfunction "P$4_S28") (pintype "bidirectional"))
    )
    (net (code "42") (name "/LEDPWM3") (class "Default")
      (node (ref "APPLICATION_") (pin "S29") (pinfunction "P$5_S29") (pintype "bidirectional"))
      (node (ref "MICRO_") (pin "S29") (pinfunction "P$5_S29") (pintype "bidirectional"))
    )
    (net (code "43") (name "/LEDPWM4") (class "Default")
      (node (ref "APPLICATION_") (pin "S30") (pinfunction "P$6_S30") (pintype "bidirectional"))
      (node (ref "MICRO_") (pin "S30") (pinfunction "P$6_S30") (pintype "bidirectional"))
    )
    (net (code "44") (name "/LEDPWM5") (class "Default")
      (node (ref "APPLICATION_") (pin "S31") (pinfunction "P$7_S31") (pintype "bidirectional"))
      (node (ref "MICRO_") (pin "S31") (pinfunction "P$7_S31") (pintype "bidirectional"))
    )
    (net (code "45") (name "/LEDPWR1") (class "Default")
      (node (ref "APPLICATION_") (pin "P1.1") (pinfunction "P$1_P1.1") (pintype "bidirectional"))
      (node (ref "APPLICATION_") (pin "P1.2") (pinfunction "P$1_P1.2") (pintype "bidirectional"))
      (node (ref "APPLICATION_") (pin "P1.3") (pinfunction "P$1_P1.3") (pintype "bidirectional"))
      (node (ref "APPLICATION_") (pin "P1.4") (pinfunction "P$1_P1.4") (pintype "bidirectional"))
      (node (ref "APPLICATION_") (pin "P1.5") (pinfunction "P$1_P1.5") (pintype "bidirectional"))
      (node (ref "APPLICATION_") (pin "P1.6") (pinfunction "P$1_P1.6") (pintype "bidirectional"))
      (node (ref "APPLICATION_") (pin "P1.7") (pinfunction "P$1_P1.7") (pintype "bidirectional"))
      (node (ref "APPLICATION_") (pin "P1.8") (pinfunction "P$1_P1.8") (pintype "bidirectional"))
      (node (ref "LEDCAMERA_1") (pin "C3") (pinfunction "C3_C3") (pintype "bidirectional"))
    )
    (net (code "46") (name "/LEDPWR2") (class "Default")
      (node (ref "APPLICATION_") (pin "P2.1") (pinfunction "P$2_P2.1") (pintype "bidirectional"))
      (node (ref "APPLICATION_") (pin "P2.2") (pinfunction "P$2_P2.2") (pintype "bidirectional"))
      (node (ref "APPLICATION_") (pin "P2.3") (pinfunction "P$2_P2.3") (pintype "bidirectional"))
      (node (ref "APPLICATION_") (pin "P2.4") (pinfunction "P$2_P2.4") (pintype "bidirectional"))
      (node (ref "APPLICATION_") (pin "P2.5") (pinfunction "P$2_P2.5") (pintype "bidirectional"))
      (node (ref "APPLICATION_") (pin "P2.6") (pinfunction "P$2_P2.6") (pintype "bidirectional"))
      (node (ref "APPLICATION_") (pin "P2.7") (pinfunction "P$2_P2.7") (pintype "bidirectional"))
      (node (ref "APPLICATION_") (pin "P2.8") (pinfunction "P$2_P2.8") (pintype "bidirectional"))
      (node (ref "LEDCAMERA_2") (pin "C3") (pinfunction "C3_C3") (pintype "bidirectional"))
    )
    (net (code "47") (name "/LEDPWR3") (class "Default")
      (node (ref "APPLICATION_") (pin "P3.1") (pinfunction "P$3_P3.1") (pintype "bidirectional"))
      (node (ref "APPLICATION_") (pin "P3.2") (pinfunction "P$3_P3.2") (pintype "bidirectional"))
      (node (ref "APPLICATION_") (pin "P3.3") (pinfunction "P$3_P3.3") (pintype "bidirectional"))
      (node (ref "APPLICATION_") (pin "P3.4") (pinfunction "P$3_P3.4") (pintype "bidirectional"))
      (node (ref "APPLICATION_") (pin "P3.5") (pinfunction "P$3_P3.5") (pintype "bidirectional"))
      (node (ref "APPLICATION_") (pin "P3.6") (pinfunction "P$3_P3.6") (pintype "bidirectional"))
      (node (ref "APPLICATION_") (pin "P3.7") (pinfunction "P$3_P3.7") (pintype "bidirectional"))
      (node (ref "APPLICATION_") (pin "P3.8") (pinfunction "P$3_P3.8") (pintype "bidirectional"))
      (node (ref "LEDCAMERA_3") (pin "C3") (pinfunction "C3_C3") (pintype "bidirectional"))
    )
    (net (code "48") (name "/LEDPWR4") (class "Default")
      (node (ref "APPLICATION_") (pin "P4.1") (pinfunction "P$4_P4.1") (pintype "bidirectional"))
      (node (ref "APPLICATION_") (pin "P4.2") (pinfunction "P$4_P4.2") (pintype "bidirectional"))
      (node (ref "APPLICATION_") (pin "P4.3") (pinfunction "P$4_P4.3") (pintype "bidirectional"))
      (node (ref "APPLICATION_") (pin "P4.4") (pinfunction "P$4_P4.4") (pintype "bidirectional"))
      (node (ref "APPLICATION_") (pin "P4.5") (pinfunction "P$4_P4.5") (pintype "bidirectional"))
      (node (ref "APPLICATION_") (pin "P4.6") (pinfunction "P$4_P4.6") (pintype "bidirectional"))
      (node (ref "APPLICATION_") (pin "P4.7") (pinfunction "P$4_P4.7") (pintype "bidirectional"))
      (node (ref "APPLICATION_") (pin "P4.8") (pinfunction "P$4_P4.8") (pintype "bidirectional"))
      (node (ref "LEDCAMERA_4") (pin "C3") (pinfunction "C3_C3") (pintype "bidirectional"))
    )
    (net (code "49") (name "/LEDPWR5") (class "Default")
      (node (ref "APPLICATION_") (pin "P5.1") (pinfunction "P$5_P5.1") (pintype "bidirectional"))
      (node (ref "APPLICATION_") (pin "P5.2") (pinfunction "P$5_P5.2") (pintype "bidirectional"))
      (node (ref "APPLICATION_") (pin "P5.3") (pinfunction "P$5_P5.3") (pintype "bidirectional"))
      (node (ref "APPLICATION_") (pin "P5.4") (pinfunction "P$5_P5.4") (pintype "bidirectional"))
      (node (ref "APPLICATION_") (pin "P5.5") (pinfunction "P$5_P5.5") (pintype "bidirectional"))
      (node (ref "APPLICATION_") (pin "P5.6") (pinfunction "P$5_P5.6") (pintype "bidirectional"))
      (node (ref "APPLICATION_") (pin "P5.7") (pinfunction "P$5_P5.7") (pintype "bidirectional"))
      (node (ref "APPLICATION_") (pin "P5.8") (pinfunction "P$5_P5.8") (pintype "bidirectional"))
      (node (ref "LEDCAMERA_5") (pin "C4") (pinfunction "C4_C4") (pintype "bidirectional"))
    )
    (net (code "50") (name "/MCOM+") (class "Default")
      (node (ref "MICRO_") (pin "S19") (pinfunction "P$3_S19") (pintype "bidirectional"))
      (node (ref "MOTOR_1") (pin "C3") (pinfunction "C3_C3") (pintype "bidirectional"))
      (node (ref "MOTOR_2") (pin "C3") (pinfunction "C3_C3") (pintype "bidirectional"))
      (node (ref "MOTOR_3") (pin "C3") (pinfunction "C3_C3") (pintype "bidirectional"))
      (node (ref "MOTOR_4") (pin "C3") (pinfunction "C3_C3") (pintype "bidirectional"))
      (node (ref "MOTOR_5") (pin "C3") (pinfunction "C3_C3") (pintype "bidirectional"))
      (node (ref "MOTOR_6") (pin "C3") (pinfunction "C3_C3") (pintype "bidirectional"))
      (node (ref "MOTOR_7") (pin "C3") (pinfunction "C3_C3") (pintype "bidirectional"))
      (node (ref "MOTOR_8") (pin "C3") (pinfunction "C3_C3") (pintype "bidirectional"))
      (node (ref "R1") (pin "2") (pinfunction "2_2") (pintype "passive"))
      (node (ref "R2") (pin "2") (pinfunction "2_2") (pintype "passive"))
    )
    (net (code "51") (name "/MCOM-") (class "Default")
      (node (ref "MICRO_") (pin "S18") (pinfunction "P$2_S18") (pintype "bidirectional"))
      (node (ref "MOTOR_1") (pin "C4") (pinfunction "C4_C4") (pintype "bidirectional"))
      (node (ref "MOTOR_2") (pin "C4") (pinfunction "C4_C4") (pintype "bidirectional"))
      (node (ref "MOTOR_3") (pin "C4") (pinfunction "C4_C4") (pintype "bidirectional"))
      (node (ref "MOTOR_4") (pin "C4") (pinfunction "C4_C4") (pintype "bidirectional"))
      (node (ref "MOTOR_5") (pin "C4") (pinfunction "C4_C4") (pintype "bidirectional"))
      (node (ref "MOTOR_6") (pin "C4") (pinfunction "C4_C4") (pintype "bidirectional"))
      (node (ref "MOTOR_7") (pin "C4") (pinfunction "C4_C4") (pintype "bidirectional"))
      (node (ref "MOTOR_8") (pin "C4") (pinfunction "C4_C4") (pintype "bidirectional"))
      (node (ref "R1") (pin "1") (pinfunction "1_1") (pintype "passive"))
      (node (ref "R2") (pin "1") (pinfunction "1_1") (pintype "passive"))
    )
    (net (code "52") (name "/N$21") (class "Default")
      (node (ref "PWRCONV_") (pin "S3") (pinfunction "P$3_S3") (pintype "bidirectional"))
    )
    (net (code "53") (name "/N$22") (class "Default")
      (node (ref "PWRCONV_") (pin "S4") (pinfunction "P$4_S4") (pintype "bidirectional"))
    )
    (net (code "54") (name "/N$23") (class "Default")
      (node (ref "PWRCONV_") (pin "S5") (pinfunction "P$5_S5") (pintype "bidirectional"))
    )
    (net (code "55") (name "/N$24") (class "Default")
      (node (ref "PWRCONV_") (pin "S6") (pinfunction "P$6_S6") (pintype "bidirectional"))
    )
    (net (code "56") (name "/N$25") (class "Default")
      (node (ref "PWRCONV_") (pin "S7") (pinfunction "P$7_S7") (pintype "bidirectional"))
    )
    (net (code "57") (name "/N$26") (class "Default")
      (node (ref "PWRCONV_") (pin "S8") (pinfunction "P$8_S8") (pintype "bidirectional"))
    )
    (net (code "58") (name "/N$27") (class "Default")
      (node (ref "PWRCONV_") (pin "S9") (pinfunction "P$1_S9") (pintype "bidirectional"))
    )
    (net (code "59") (name "/N$28") (class "Default")
      (node (ref "PWRCONV_") (pin "S10") (pinfunction "P$2_S10") (pintype "bidirectional"))
    )
    (net (code "60") (name "/N$29") (class "Default")
      (node (ref "PWRCONV_") (pin "S11") (pinfunction "P$3_S11") (pintype "bidirectional"))
    )
    (net (code "61") (name "/N$30") (class "Default")
      (node (ref "PWRCONV_") (pin "S12") (pinfunction "P$4_S12") (pintype "bidirectional"))
    )
    (net (code "62") (name "/N$31") (class "Default")
      (node (ref "PWRCONV_") (pin "S13") (pinfunction "P$5_S13") (pintype "bidirectional"))
    )
    (net (code "63") (name "/N$32") (class "Default")
      (node (ref "PWRCONV_") (pin "S14") (pinfunction "P$6_S14") (pintype "bidirectional"))
    )
    (net (code "64") (name "/N$33") (class "Default")
      (node (ref "PWRCONV_") (pin "S15") (pinfunction "P$7_S15") (pintype "bidirectional"))
    )
    (net (code "65") (name "/N$36") (class "Default")
      (node (ref "PWRCONV_") (pin "S18") (pinfunction "P$2_S18") (pintype "bidirectional"))
    )
    (net (code "66") (name "/N$37") (class "Default")
      (node (ref "PWRCONV_") (pin "S19") (pinfunction "P$3_S19") (pintype "bidirectional"))
    )
    (net (code "67") (name "/N$38") (class "Default")
      (node (ref "PWRCONV_") (pin "S20") (pinfunction "P$4_S20") (pintype "bidirectional"))
    )
    (net (code "68") (name "/N$39") (class "Default")
      (node (ref "PWRCONV_") (pin "S21") (pinfunction "P$5_S21") (pintype "bidirectional"))
    )
    (net (code "69") (name "/N$40") (class "Default")
      (node (ref "PWRCONV_") (pin "S22") (pinfunction "P$6_S22") (pintype "bidirectional"))
    )
    (net (code "70") (name "/N$41") (class "Default")
      (node (ref "PWRCONV_") (pin "S23") (pinfunction "P$7_S23") (pintype "bidirectional"))
    )
    (net (code "71") (name "/N$155") (class "Default")
      (node (ref "COMM") (pin "S1") (pinfunction "P$1_S1") (pintype "bidirectional"))
    )
    (net (code "72") (name "/N$156") (class "Default")
      (node (ref "COMM") (pin "S2") (pinfunction "P$2_S2") (pintype "bidirectional"))
    )
    (net (code "73") (name "/N$168") (class "Default")
      (node (ref "COMM") (pin "S14") (pinfunction "P$6_S14") (pintype "bidirectional"))
    )
    (net (code "74") (name "/N$169") (class "Default")
      (node (ref "COMM") (pin "S15") (pinfunction "P$7_S15") (pintype "bidirectional"))
    )
    (net (code "75") (name "/S1") (class "Default")
      (node (ref "APPLICATION_") (pin "S1") (pinfunction "P$1_S1") (pintype "bidirectional"))
      (node (ref "MICRO_") (pin "S1") (pinfunction "P$1_S1") (pintype "bidirectional"))
    )
    (net (code "76") (name "/S2") (class "Default")
      (node (ref "APPLICATION_") (pin "S2") (pinfunction "P$2_S2") (pintype "bidirectional"))
      (node (ref "MICRO_") (pin "S2") (pinfunction "P$2_S2") (pintype "bidirectional"))
    )
    (net (code "77") (name "/S3") (class "Default")
      (node (ref "APPLICATION_") (pin "S3") (pinfunction "P$3_S3") (pintype "bidirectional"))
      (node (ref "MICRO_") (pin "S3") (pinfunction "P$3_S3") (pintype "bidirectional"))
    )
    (net (code "78") (name "/S4") (class "Default")
      (node (ref "APPLICATION_") (pin "S4") (pinfunction "P$4_S4") (pintype "bidirectional"))
      (node (ref "MICRO_") (pin "S4") (pinfunction "P$4_S4") (pintype "bidirectional"))
    )
    (net (code "79") (name "/S5") (class "Default")
      (node (ref "APPLICATION_") (pin "S5") (pinfunction "P$5_S5") (pintype "bidirectional"))
      (node (ref "MICRO_") (pin "S5") (pinfunction "P$5_S5") (pintype "bidirectional"))
    )
    (net (code "80") (name "/S11") (class "Default")
      (node (ref "MICRO_") (pin "S11") (pinfunction "P$3_S11") (pintype "bidirectional"))
    )
    (net (code "81") (name "/S12") (class "Default")
      (node (ref "MICRO_") (pin "S12") (pinfunction "P$4_S12") (pintype "bidirectional"))
    )
    (net (code "82") (name "/S13") (class "Default")
      (node (ref "MICRO_") (pin "S13") (pinfunction "P$5_S13") (pintype "bidirectional"))
    )
    (net (code "83") (name "/S14") (class "Default")
      (node (ref "MICRO_") (pin "S14") (pinfunction "P$6_S14") (pintype "bidirectional"))
    )
    (net (code "84") (name "/S15") (class "Default")
      (node (ref "MICRO_") (pin "S15") (pinfunction "P$7_S15") (pintype "bidirectional"))
    )
    (net (code "85") (name "/S23") (class "Default")
      (node (ref "APPLICATION_") (pin "S23") (pinfunction "P$7_S23") (pintype "bidirectional"))
    )
    (net (code "86") (name "/S24") (class "Default")
      (node (ref "APPLICATION_") (pin "S24") (pinfunction "P$8_S24") (pintype "bidirectional"))
    )
    (net (code "87") (name "/S32") (class "Default")
      (node (ref "MICRO_") (pin "S32") (pinfunction "P$8_S32") (pintype "bidirectional"))
    )
    (net (code "88") (name "/S45") (class "Default")
      (node (ref "APPLICATION_") (pin "S45") (pinfunction "P$5_S45") (pintype "bidirectional"))
    )
    (net (code "89") (name "/S46") (class "Default")
      (node (ref "APPLICATION_") (pin "S46") (pinfunction "P$6_S46") (pintype "bidirectional"))
    )
    (net (code "90") (name "/SERVO1CURRENT") (class "Default")
      (node (ref "APPLICATION_") (pin "S36") (pinfunction "P$4_S36") (pintype "bidirectional"))
      (node (ref "MICRO_") (pin "S36") (pinfunction "P$4_S36") (pintype "bidirectional"))
    )
    (net (code "91") (name "/SERVO1PWM") (class "Default")
      (node (ref "CLAWSERVO_1") (pin "C3") (pinfunction "C3_C3") (pintype "bidirectional"))
      (node (ref "MICRO_") (pin "S20") (pinfunction "P$4_S20") (pintype "bidirectional"))
    )
    (net (code "92") (name "/SERVO2CURRENT") (class "Default")
      (node (ref "APPLICATION_") (pin "S35") (pinfunction "P$3_S35") (pintype "bidirectional"))
      (node (ref "MICRO_") (pin "S35") (pinfunction "P$3_S35") (pintype "bidirectional"))
    )
    (net (code "93") (name "/SERVO2PWM") (class "Default")
      (node (ref "CLAWSERVO_2") (pin "C3") (pinfunction "C3_C3") (pintype "bidirectional"))
      (node (ref "MICRO_") (pin "S21") (pinfunction "P$5_S21") (pintype "bidirectional"))
    )
    (net (code "94") (name "/STEP1") (class "Default")
      (node (ref "APPLICATION_") (pin "S33") (pinfunction "P$1_S33") (pintype "bidirectional"))
      (node (ref "MICRO_") (pin "S33") (pinfunction "P$1_S33") (pintype "bidirectional"))
    )
    (net (code "95") (name "/STEP1A1") (class "Default")
      (node (ref "APPLICATION_") (pin "S13") (pinfunction "P$5_S13") (pintype "bidirectional"))
      (node (ref "STEPPER_1") (pin "C1") (pinfunction "C1_C1") (pintype "bidirectional"))
    )
    (net (code "96") (name "/STEP1A2") (class "Default")
      (node (ref "APPLICATION_") (pin "S14") (pinfunction "P$6_S14") (pintype "bidirectional"))
      (node (ref "STEPPER_1") (pin "C2") (pinfunction "C2_C2") (pintype "bidirectional"))
    )
    (net (code "97") (name "/STEP1B1") (class "Default")
      (node (ref "APPLICATION_") (pin "S15") (pinfunction "P$7_S15") (pintype "bidirectional"))
      (node (ref "STEPPER_1") (pin "C3") (pinfunction "C3_C3") (pintype "bidirectional"))
    )
    (net (code "98") (name "/STEP1B2") (class "Default")
      (node (ref "APPLICATION_") (pin "S16") (pinfunction "P$8_S16") (pintype "bidirectional"))
      (node (ref "STEPPER_1") (pin "C4") (pinfunction "C4_C4") (pintype "bidirectional"))
    )
    (net (code "99") (name "/STEP2") (class "Default")
      (node (ref "APPLICATION_") (pin "S43") (pinfunction "P$3_S43") (pintype "bidirectional"))
      (node (ref "MICRO_") (pin "S43") (pinfunction "P$3_S43") (pintype "bidirectional"))
    )
    (net (code "100") (name "/STEP2A1") (class "Default")
      (node (ref "APPLICATION_") (pin "S9") (pinfunction "P$1_S9") (pintype "bidirectional"))
      (node (ref "STEPPER_2") (pin "C1") (pinfunction "C1_C1") (pintype "bidirectional"))
    )
    (net (code "101") (name "/STEP2A2") (class "Default")
      (node (ref "APPLICATION_") (pin "S10") (pinfunction "P$2_S10") (pintype "bidirectional"))
      (node (ref "STEPPER_2") (pin "C2") (pinfunction "C2_C2") (pintype "bidirectional"))
    )
    (net (code "102") (name "/STEP2B1") (class "Default")
      (node (ref "APPLICATION_") (pin "S11") (pinfunction "P$3_S11") (pintype "bidirectional"))
      (node (ref "STEPPER_2") (pin "C3") (pinfunction "C3_C3") (pintype "bidirectional"))
    )
    (net (code "103") (name "/STEP2B2") (class "Default")
      (node (ref "APPLICATION_") (pin "S12") (pinfunction "P$4_S12") (pintype "bidirectional"))
      (node (ref "STEPPER_2") (pin "C4") (pinfunction "C4_C4") (pintype "bidirectional"))
    )
    (net (code "104") (name "/STEPDIR1") (class "Default")
      (node (ref "APPLICATION_") (pin "S44") (pinfunction "P$4_S44") (pintype "bidirectional"))
      (node (ref "MICRO_") (pin "S44") (pinfunction "P$4_S44") (pintype "bidirectional"))
    )
    (net (code "105") (name "/STEPDIR2") (class "Default")
      (node (ref "APPLICATION_") (pin "S42") (pinfunction "P$2_S42") (pintype "bidirectional"))
      (node (ref "MICRO_") (pin "S42") (pinfunction "P$2_S42") (pintype "bidirectional"))
    )
    (net (code "106") (name "/STEPEN") (class "Default")
      (node (ref "APPLICATION_") (pin "S34") (pinfunction "P$2_S34") (pintype "bidirectional"))
      (node (ref "MICRO_") (pin "S34") (pinfunction "P$2_S34") (pintype "bidirectional"))
    )
    (net (code "107") (name "/TETHER_RX") (class "Default")
      (node (ref "COMM") (pin "S18") (pinfunction "P$2_S18") (pintype "bidirectional"))
      (node (ref "MICRO_") (pin "S46") (pinfunction "P$6_S46") (pintype "bidirectional"))
    )
    (net (code "108") (name "/TETHER_TX") (class "Default")
      (node (ref "COMM") (pin "S17") (pinfunction "P$1_S17") (pintype "bidirectional"))
      (node (ref "MICRO_") (pin "S45") (pinfunction "P$5_S45") (pintype "bidirectional"))
    )
    (net (code "109") (name "/TURN+") (class "Default")
      (node (ref "APPLICATION_") (pin "P8.1") (pinfunction "P$2_P8.1") (pintype "bidirectional"))
      (node (ref "APPLICATION_") (pin "P8.2") (pinfunction "P$2_P8.2") (pintype "bidirectional"))
      (node (ref "APPLICATION_") (pin "P8.3") (pinfunction "P$2_P8.3") (pintype "bidirectional"))
      (node (ref "APPLICATION_") (pin "P8.4") (pinfunction "P$2_P8.4") (pintype "bidirectional"))
      (node (ref "APPLICATION_") (pin "P8.5") (pinfunction "P$2_P8.5") (pintype "bidirectional"))
      (node (ref "APPLICATION_") (pin "P8.6") (pinfunction "P$2_P8.6") (pintype "bidirectional"))
      (node (ref "APPLICATION_") (pin "P8.7") (pinfunction "P$2_P8.7") (pintype "bidirectional"))
      (node (ref "APPLICATION_") (pin "P8.8") (pinfunction "P$2_P8.8") (pintype "bidirectional"))
      (node (ref "TURNINGMOTOR") (pin "C1") (pinfunction "C1_C1") (pintype "bidirectional"))
      (node (ref "TURNINGMOTOR") (pin "C2") (pinfunction "C2_C2") (pintype "bidirectional"))
    )
    (net (code "110") (name "/TURN-") (class "Default")
      (node (ref "APPLICATION_") (pin "P9.1") (pinfunction "P$3_P9.1") (pintype "bidirectional"))
      (node (ref "APPLICATION_") (pin "P9.2") (pinfunction "P$3_P9.2") (pintype "bidirectional"))
      (node (ref "APPLICATION_") (pin "P9.3") (pinfunction "P$3_P9.3") (pintype "bidirectional"))
      (node (ref "APPLICATION_") (pin "P9.4") (pinfunction "P$3_P9.4") (pintype "bidirectional"))
      (node (ref "APPLICATION_") (pin "P9.5") (pinfunction "P$3_P9.5") (pintype "bidirectional"))
      (node (ref "APPLICATION_") (pin "P9.6") (pinfunction "P$3_P9.6") (pintype "bidirectional"))
      (node (ref "APPLICATION_") (pin "P9.7") (pinfunction "P$3_P9.7") (pintype "bidirectional"))
      (node (ref "APPLICATION_") (pin "P9.8") (pinfunction "P$3_P9.8") (pintype "bidirectional"))
      (node (ref "TURNINGMOTOR") (pin "C3") (pinfunction "C3_C3") (pintype "bidirectional"))
      (node (ref "TURNINGMOTOR") (pin "C4") (pinfunction "C4_C4") (pintype "bidirectional"))
    )
    (net (code "111") (name "/TURNCURRENT") (class "Default")
      (node (ref "APPLICATION_") (pin "S37") (pinfunction "P$5_S37") (pintype "bidirectional"))
      (node (ref "MICRO_") (pin "S37") (pinfunction "P$5_S37") (pintype "bidirectional"))
    )
    (net (code "112") (name "/TURNPWM1") (class "Default")
      (node (ref "APPLICATION_") (pin "S39") (pinfunction "P$7_S39") (pintype "bidirectional"))
      (node (ref "MICRO_") (pin "S39") (pinfunction "P$7_S39") (pintype "bidirectional"))
    )
    (net (code "113") (name "/TURNPWM2") (class "Default")
      (node (ref "APPLICATION_") (pin "S38") (pinfunction "P$6_S38") (pintype "bidirectional"))
      (node (ref "MICRO_") (pin "S38") (pinfunction "P$6_S38") (pintype "bidirectional"))
    )
    (net (code "114") (name "/VIDEO1") (class "Default")
      (node (ref "COMM") (pin "S5") (pinfunction "P$5_S5") (pintype "bidirectional"))
      (node (ref "LEDCAMERA_1") (pin "C4") (pinfunction "C4_C4") (pintype "bidirectional"))
    )
    (net (code "115") (name "/VIDEO2") (class "Default")
      (node (ref "COMM") (pin "S6") (pinfunction "P$6_S6") (pintype "bidirectional"))
      (node (ref "LEDCAMERA_2") (pin "C4") (pinfunction "C4_C4") (pintype "bidirectional"))
    )
    (net (code "116") (name "/VIDEO3") (class "Default")
      (node (ref "COMM") (pin "S7") (pinfunction "P$7_S7") (pintype "bidirectional"))
      (node (ref "LEDCAMERA_3") (pin "C4") (pinfunction "C4_C4") (pintype "bidirectional"))
    )
    (net (code "117") (name "/VIDEO4") (class "Default")
      (node (ref "COMM") (pin "S8") (pinfunction "P$8_S8") (pintype "bidirectional"))
      (node (ref "LEDCAMERA_4") (pin "C4") (pinfunction "C4_C4") (pintype "bidirectional"))
    )
    (net (code "118") (name "/VOUT1") (class "Default")
      (node (ref "ALTVIDEO") (pin "C1") (pinfunction "C1_C1") (pintype "bidirectional"))
      (node (ref "COMM") (pin "S4") (pinfunction "P$4_S4") (pintype "bidirectional"))
    )
    (net (code "119") (name "/VOUT2") (class "Default")
      (node (ref "ALTVIDEO") (pin "C3") (pinfunction "C3_C3") (pintype "bidirectional"))
      (node (ref "COMM") (pin "S3") (pinfunction "P$3_S3") (pintype "bidirectional"))
    )
    (net (code "120") (name "/VPROBE1") (class "Default")
      (node (ref "APPLICATION_") (pin "S19") (pinfunction "P$3_S19") (pintype "bidirectional"))
      (node (ref "VSENSE") (pin "C2") (pinfunction "C2_C2") (pintype "bidirectional"))
    )
    (net (code "121") (name "/VPROBE2") (class "Default")
      (node (ref "APPLICATION_") (pin "S18") (pinfunction "P$2_S18") (pintype "bidirectional"))
      (node (ref "VSENSE") (pin "C3") (pinfunction "C3_C3") (pintype "bidirectional"))
    )
    (net (code "122") (name "/VPROBE3") (class "Default")
      (node (ref "APPLICATION_") (pin "S17") (pinfunction "P$1_S17") (pintype "bidirectional"))
      (node (ref "VSENSE") (pin "C4") (pinfunction "C4_C4") (pintype "bidirectional"))
    )
    (net (code "123") (name "/VSEL1") (class "Default")
      (node (ref "COMM") (pin "S19") (pinfunction "P$3_S19") (pintype "bidirectional"))
      (node (ref "MICRO_") (pin "S47") (pinfunction "P$7_S47") (pintype "bidirectional"))
    )
    (net (code "124") (name "/VSEL2") (class "Default")
      (node (ref "COMM") (pin "S20") (pinfunction "P$4_S20") (pintype "bidirectional"))
      (node (ref "MICRO_") (pin "S48") (pinfunction "P$8_S48") (pintype "bidirectional"))
    )
    (net (code "125") (name "/VSEN1") (class "Default")
      (node (ref "APPLICATION_") (pin "S8") (pinfunction "P$8_S8") (pintype "bidirectional"))
      (node (ref "MICRO_") (pin "S8") (pinfunction "P$8_S8") (pintype "bidirectional"))
    )
    (net (code "126") (name "/VSEN2") (class "Default")
      (node (ref "APPLICATION_") (pin "S7") (pinfunction "P$7_S7") (pintype "bidirectional"))
      (node (ref "MICRO_") (pin "S7") (pinfunction "P$7_S7") (pintype "bidirectional"))
    )
    (net (code "127") (name "/VSEN3") (class "Default")
      (node (ref "APPLICATION_") (pin "S6") (pinfunction "P$6_S6") (pintype "bidirectional"))
      (node (ref "MICRO_") (pin "S6") (pinfunction "P$6_S6") (pintype "bidirectional"))
    )
    (net (code "128") (name "GND") (class "Default")
      (node (ref "ALTVIDEO") (pin "C2") (pinfunction "C2_C2") (pintype "bidirectional"))
      (node (ref "ALTVIDEO") (pin "C4") (pinfunction "C4_C4") (pintype "bidirectional"))
      (node (ref "APPLICATION_") (pin "P11.1") (pinfunction "P$5_P11.1") (pintype "bidirectional"))
      (node (ref "APPLICATION_") (pin "P11.2") (pinfunction "P$5_P11.2") (pintype "bidirectional"))
      (node (ref "APPLICATION_") (pin "P11.3") (pinfunction "P$5_P11.3") (pintype "bidirectional"))
      (node (ref "APPLICATION_") (pin "P11.4") (pinfunction "P$5_P11.4") (pintype "bidirectional"))
      (node (ref "APPLICATION_") (pin "P11.5") (pinfunction "P$5_P11.5") (pintype "bidirectional"))
      (node (ref "APPLICATION_") (pin "P11.6") (pinfunction "P$5_P11.6") (pintype "bidirectional"))
      (node (ref "APPLICATION_") (pin "P11.7") (pinfunction "P$5_P11.7") (pintype "bidirectional"))
      (node (ref "APPLICATION_") (pin "P11.8") (pinfunction "P$5_P11.8") (pintype "bidirectional"))
      (node (ref "BILGEPUMP") (pin "C1") (pinfunction "C1_C1") (pintype "bidirectional"))
      (node (ref "BILGEPUMP") (pin "C2") (pinfunction "C2_C2") (pintype "bidirectional"))
      (node (ref "CLAWSERVO_1") (pin "C1") (pinfunction "C1_C1") (pintype "bidirectional"))
      (node (ref "CLAWSERVO_2") (pin "C1") (pinfunction "C1_C1") (pintype "bidirectional"))
      (node (ref "COMM") (pin "S13") (pinfunction "P$5_S13") (pintype "bidirectional"))
      (node (ref "COMM") (pin "S9") (pinfunction "P$1_S9") (pintype "bidirectional"))
      (node (ref "LASER") (pin "C2") (pinfunction "C2_C2") (pintype "bidirectional"))
      (node (ref "LASER2") (pin "C3") (pinfunction "C3_C3") (pintype "bidirectional"))
      (node (ref "LEDCAMERA_1") (pin "C1") (pinfunction "C1_C1") (pintype "bidirectional"))
      (node (ref "LEDCAMERA_2") (pin "C1") (pinfunction "C1_C1") (pintype "bidirectional"))
      (node (ref "LEDCAMERA_3") (pin "C1") (pinfunction "C1_C1") (pintype "bidirectional"))
      (node (ref "LEDCAMERA_4") (pin "C1") (pinfunction "C1_C1") (pintype "bidirectional"))
      (node (ref "LEDCAMERA_5") (pin "C1") (pinfunction "C1_C1") (pintype "bidirectional"))
      (node (ref "MICRO_") (pin "P4.1") (pinfunction "P$4_P4.1") (pintype "bidirectional"))
      (node (ref "MICRO_") (pin "P4.2") (pinfunction "P$4_P4.2") (pintype "bidirectional"))
      (node (ref "MICRO_") (pin "P4.3") (pinfunction "P$4_P4.3") (pintype "bidirectional"))
      (node (ref "MICRO_") (pin "P4.4") (pinfunction "P$4_P4.4") (pintype "bidirectional"))
      (node (ref "MICRO_") (pin "P4.5") (pinfunction "P$4_P4.5") (pintype "bidirectional"))
      (node (ref "MICRO_") (pin "P4.6") (pinfunction "P$4_P4.6") (pintype "bidirectional"))
      (node (ref "MICRO_") (pin "P4.7") (pinfunction "P$4_P4.7") (pintype "bidirectional"))
      (node (ref "MICRO_") (pin "P4.8") (pinfunction "P$4_P4.8") (pintype "bidirectional"))
      (node (ref "MOTORDIST_") (pin "P11.1") (pinfunction "P$5_P11.1") (pintype "bidirectional"))
      (node (ref "MOTORDIST_") (pin "P11.2") (pinfunction "P$5_P11.2") (pintype "bidirectional"))
      (node (ref "MOTORDIST_") (pin "P11.3") (pinfunction "P$5_P11.3") (pintype "bidirectional"))
      (node (ref "MOTORDIST_") (pin "P11.4") (pinfunction "P$5_P11.4") (pintype "bidirectional"))
      (node (ref "MOTORDIST_") (pin "P11.5") (pinfunction "P$5_P11.5") (pintype "bidirectional"))
      (node (ref "MOTORDIST_") (pin "P11.6") (pinfunction "P$5_P11.6") (pintype "bidirectional"))
      (node (ref "MOTORDIST_") (pin "P11.7") (pinfunction "P$5_P11.7") (pintype "bidirectional"))
      (node (ref "MOTORDIST_") (pin "P11.8") (pinfunction "P$5_P11.8") (pintype "bidirectional"))
      (node (ref "MOTOR_1") (pin "C2") (pinfunction "C2_C2") (pintype "bidirectional"))
      (node (ref "MOTOR_2") (pin "C2") (pinfunction "C2_C2") (pintype "bidirectional"))
      (node (ref "MOTOR_3") (pin "C2") (pinfunction "C2_C2") (pintype "bidirectional"))
      (node (ref "MOTOR_4") (pin "C2") (pinfunction "C2_C2") (pintype "bidirectional"))
      (node (ref "MOTOR_5") (pin "C2") (pinfunction "C2_C2") (pintype "bidirectional"))
      (node (ref "MOTOR_6") (pin "C2") (pinfunction "C2_C2") (pintype "bidirectional"))
      (node (ref "MOTOR_7") (pin "C2") (pinfunction "C2_C2") (pintype "bidirectional"))
      (node (ref "MOTOR_8") (pin "C2") (pinfunction "C2_C2") (pintype "bidirectional"))
      (node (ref "PWRCONV_") (pin "P5.1") (pinfunction "P$5_P5.1") (pintype "bidirectional"))
      (node (ref "PWRCONV_") (pin "P5.2") (pinfunction "P$5_P5.2") (pintype "bidirectional"))
      (node (ref "PWRCONV_") (pin "P5.3") (pinfunction "P$5_P5.3") (pintype "bidirectional"))
      (node (ref "PWRCONV_") (pin "P5.4") (pinfunction "P$5_P5.4") (pintype "bidirectional"))
      (node (ref "PWRCONV_") (pin "P5.5") (pinfunction "P$5_P5.5") (pintype "bidirectional"))
      (node (ref "PWRCONV_") (pin "P5.6") (pinfunction "P$5_P5.6") (pintype "bidirectional"))
      (node (ref "PWRCONV_") (pin "P5.7") (pinfunction "P$5_P5.7") (pintype "bidirectional"))
      (node (ref "PWRCONV_") (pin "P5.8") (pinfunction "P$5_P5.8") (pintype "bidirectional"))
      (node (ref "PWR_IN") (pin "P3") (pinfunction "P$2_P3") (pintype "bidirectional"))
      (node (ref "PWR_IN") (pin "P4") (pinfunction "P$2_P4") (pintype "bidirectional"))
      (node (ref "PWR_IN") (pin "P7") (pinfunction "P$2_P7") (pintype "bidirectional"))
      (node (ref "PWR_IN") (pin "P8") (pinfunction "P$2_P8") (pintype "bidirectional"))
    )
    (net (code "129") (name "unconnected-(CLAWSERVO_1-PadC4)") (class "Default")
      (node (ref "CLAWSERVO_1") (pin "C4") (pinfunction "C4_C4") (pintype "bidirectional"))
    )
    (net (code "130") (name "unconnected-(CLAWSERVO_2-PadC4)") (class "Default")
      (node (ref "CLAWSERVO_2") (pin "C4") (pinfunction "C4_C4") (pintype "bidirectional"))
    )
  )
)
